# Boost.net
KiCad netlist of a schematic drawn in Altium Designer
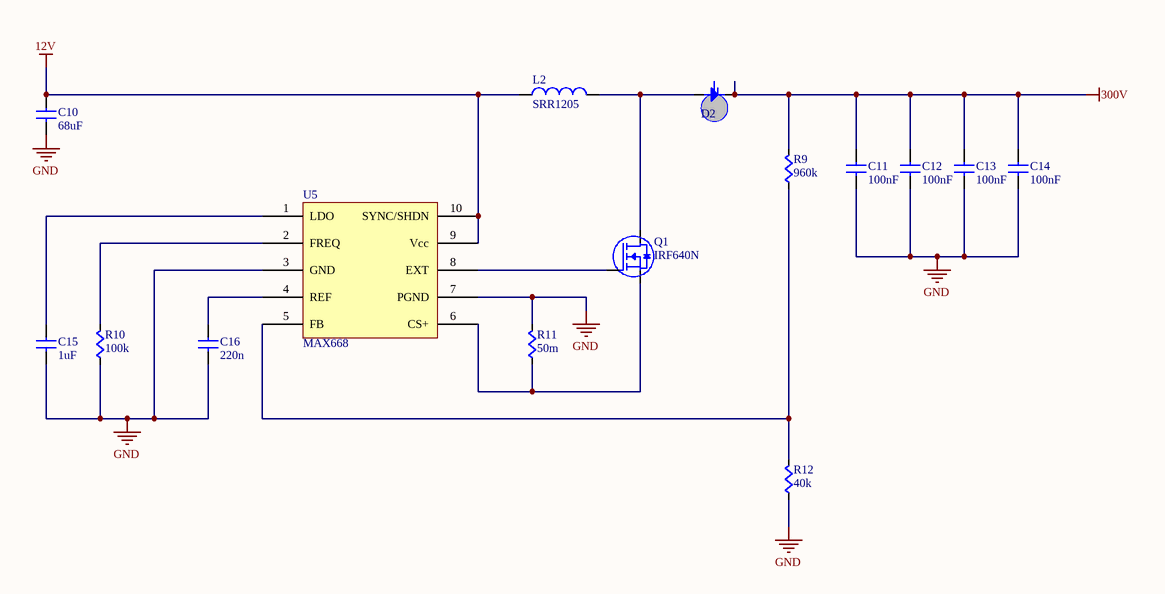
[diagram p0: Boost.SchDoc]

(export (version "E")
  (design (tool "Eeschema 10.0.6"))
  (components
    (comp (ref "C10")
      (value "68uF")
      (footprint "CAPC0603")
      (fields (field (name "Comment") "Cap"))
      (libsource (lib "Passives") (part "Cap"))
    )
    (comp (ref "C11")
      (value "100nF")
      (footprint "CAPC0603")
      (fields (field (name "Comment") "Cap"))
      (libsource (lib "Passives") (part "Cap"))
    )
    (comp (ref "C12")
      (value "100nF")
      (footprint "CAPC0603")
      (fields (field (name "Comment") "Cap"))
      (libsource (lib "Passives") (part "Cap"))
    )
    (comp (ref "C13")
      (value "100nF")
      (footprint "CAPC0603")
      (fields (field (name "Comment") "Cap"))
      (libsource (lib "Passives") (part "Cap"))
    )
    (comp (ref "C14")
      (value "100nF")
      (footprint "CAPC0603")
      (fields (field (name "Comment") "Cap"))
      (libsource (lib "Passives") (part "Cap"))
    )
    (comp (ref "C15")
      (value "1uF")
      (footprint "CAPC0402")
      (fields (field (name "Comment") "Cap"))
      (libsource (lib "Passives") (part "Cap"))
    )
    (comp (ref "C16")
      (value "220n")
      (footprint "CAPC0402")
      (fields (field (name "Comment") "Cap"))
      (libsource (lib "Passives") (part "Cap"))
    )
    (comp (ref "D2")
      (value "Diode")
      (footprint "TEMD5510FX01")
      (description "Standard Diode Template")
      (libsource (lib "Semiconductors") (part "Diode"))
    )
    (comp (ref "L2")
      (value "SRR1205")
      (footprint "SRR1205")
      (description "FIXED IND 3MH 500MA 3.5 OHM SMD")
      (libsource (lib "Sonar_Library") (part "SRR1205"))
    )
    (comp (ref "Q1")
      (value "IRF640N")
      (footprint "IRF640N")
      (description "MOSFET N-CH 200V 18A D2PAK")
      (libsource (lib "Sonar_Library") (part "IRF640N"))
    )
    (comp (ref "R9")
      (value "960k")
      (footprint "RES0603")
      (fields (field (name "Comment") "Res"))
      (libsource (lib "Passives") (part "Res"))
    )
    (comp (ref "R10")
      (value "100k")
      (footprint "RES0603")
      (fields (field (name "Comment") "Res"))
      (libsource (lib "Passives") (part "Res"))
    )
    (comp (ref "R11")
      (value "50m")
      (footprint "RES0603")
      (fields (field (name "Comment") "Res"))
      (libsource (lib "Passives") (part "Res"))
    )
    (comp (ref "R12")
      (value "40k")
      (footprint "RES0603")
      (fields (field (name "Comment") "Res"))
      (libsource (lib "Passives") (part "Res"))
    )
    (comp (ref "U5")
      (value "MAX668")
      (footprint "Sonar_Library:MAX668")
      (description "IC REG CTRLR PWM HYBRID 10-UMAX")
      (libsource (lib "Sonar_Library") (part "MAX668"))
    )
  )
  (nets
    (net (code "1") (name "12V") (class "Default")
      (node (ref "C10") (pin "1") (pinfunction "A_1") (pintype "passive"))
      (node (ref "L2") (pin "1") (pinfunction "A_1") (pintype "passive"))
      (node (ref "U5") (pin "10") (pinfunction "SYNC/SHDN_10") (pintype "passive"))
      (node (ref "U5") (pin "9") (pinfunction "Vcc_9") (pintype "passive"))
    )
    (net (code "2") (name "300V") (class "Default")
      (node (ref "C11") (pin "1") (pinfunction "A_1") (pintype "passive"))
      (node (ref "C12") (pin "1") (pinfunction "A_1") (pintype "passive"))
      (node (ref "C13") (pin "1") (pinfunction "A_1") (pintype "passive"))
      (node (ref "C14") (pin "1") (pinfunction "A_1") (pintype "passive"))
      (node (ref "D2") (pin "C") (pinfunction "C_C") (pintype "passive"))
      (node (ref "R9") (pin "1") (pinfunction "A_1") (pintype "passive"))
    )
    (net (code "3") (name "GND") (class "Default")
      (node (ref "C10") (pin "2") (pinfunction "B_2") (pintype "passive"))
      (node (ref "C11") (pin "2") (pinfunction "B_2") (pintype "passive"))
      (node (ref "C12") (pin "2") (pinfunction "B_2") (pintype "passive"))
      (node (ref "C13") (pin "2") (pinfunction "B_2") (pintype "passive"))
      (node (ref "C14") (pin "2") (pinfunction "B_2") (pintype "passive"))
      (node (ref "C15") (pin "2") (pinfunction "B_2") (pintype "passive"))
      (node (ref "C16") (pin "2") (pinfunction "B_2") (pintype "passive"))
      (node (ref "R10") (pin "2") (pinfunction "B_2") (pintype "passive"))
      (node (ref "R11") (pin "1") (pinfunction "A_1") (pintype "passive"))
      (node (ref "R12") (pin "2") (pinfunction "B_2") (pintype "passive"))
      (node (ref "U5") (pin "3") (pinfunction "GND_3") (pintype "passive"))
      (node (ref "U5") (pin "7") (pinfunction "PGND_7") (pintype "passive"))
    )
    (net (code "4") (name "Net-(C15-A)") (class "Default")
      (node (ref "C15") (pin "1") (pinfunction "A_1") (pintype "passive"))
      (node (ref "U5") (pin "1") (pinfunction "LDO_1") (pintype "passive"))
    )
    (net (code "5") (name "Net-(C16-A)") (class "Default")
      (node (ref "C16") (pin "1") (pinfunction "A_1") (pintype "passive"))
      (node (ref "U5") (pin "4") (pinfunction "REF_4") (pintype "passive"))
    )
    (net (code "6") (name "Net-(L2-B)") (class "Default")
      (node (ref "D2") (pin "A") (pinfunction "A_A") (pintype "passive"))
      (node (ref "L2") (pin "2") (pinfunction "B_2") (pintype "passive"))
      (node (ref "Q1") (pin "D") (pinfunction "D_D") (pintype "passive"))
    )
    (net (code "7") (name "Net-(R10-A)") (class "Default")
      (node (ref "R10") (pin "1") (pinfunction "A_1") (pintype "passive"))
      (node (ref "U5") (pin "2") (pinfunction "FREQ_2") (pintype "passive"))
    )
    (net (code "8") (name "Net-(R11-B)") (class "Default")
      (node (ref "Q1") (pin "S") (pinfunction "S_S") (pintype "passive"))
      (node (ref "R11") (pin "2") (pinfunction "B_2") (pintype "passive"))
      (node (ref "U5") (pin "6") (pinfunction "CS+_6") (pintype "passive"))
    )
    (net (code "9") (name "Net-(R12-A)") (class "Default")
      (node (ref "R12") (pin "1") (pinfunction "A_1") (pintype "passive"))
      (node (ref "R9") (pin "2") (pinfunction "B_2") (pintype "passive"))
      (node (ref "U5") (pin "5") (pinfunction "FB_5") (pintype "passive"))
    )
    (net (code "10") (name "Net-(U5-EXT)") (class "Default")
      (node (ref "Q1") (pin "G") (pinfunction "G_G") (pintype "passive"))
      (node (ref "U5") (pin "8") (pinfunction "EXT_8") (pintype "passive"))
    )
  )
)
